# Sheet1.net
KiCad netlist of a schematic drawn in Altium Designer
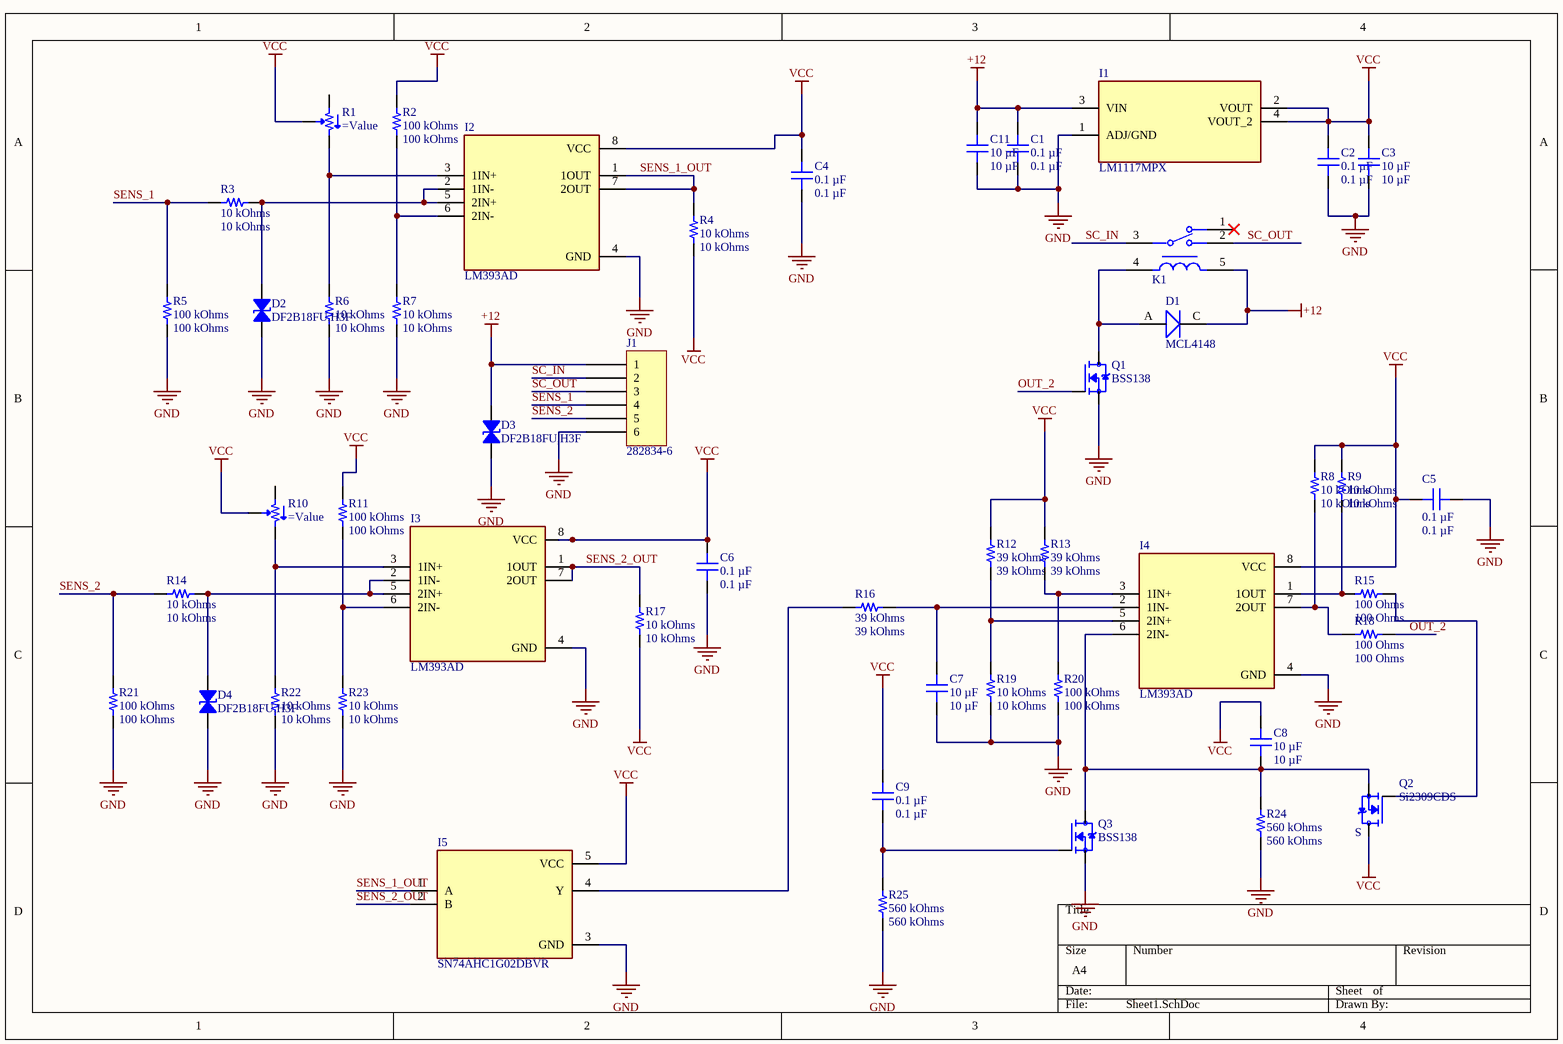
[diagram p0: Sheet1.SchDoc]

(export (version "E")
  (design (tool "Eeschema 10.0.6"))
  (components
    (comp (ref "C1")
      (value "0.1 µF")
      (footprint "CAP 0603_1608")
      (description "CAP CER 0.1UF 16V X7R 0603")
      (fields (field (name "PART NUMBER") "0603B104M160CT") (field (name "ALTIUM_VALUE") "0.1 µF"))
      (libsource (lib "Celestial Altium Library - altium_library") (part "Capacitor"))
    )
    (comp (ref "C2")
      (value "0.1 µF")
      (footprint "CAP 0603_1608")
      (description "CAP CER 0.1UF 16V X7R 0603")
      (fields (field (name "PART NUMBER") "0603B104M160CT") (field (name "ALTIUM_VALUE") "0.1 µF"))
      (libsource (lib "Celestial Altium Library - altium_library") (part "Capacitor"))
    )
    (comp (ref "C3")
      (value "10 µF")
      (footprint "CAP 1206_3216 - 0.8MM")
      (description "CAP CER 10UF 16V X7R 1206")
      (fields (field (name "PART NUMBER") "C1206C106M4RAC7800") (field (name "ALTIUM_VALUE") "10 µF"))
      (libsource (lib "Celestial Altium Library - altium_library") (part "Capacitor"))
    )
    (comp (ref "C4")
      (value "0.1 µF")
      (footprint "CAP 0603_1608")
      (description "CAP CER 0.1UF 16V X7R 0603")
      (fields (field (name "PART NUMBER") "0603B104M160CT") (field (name "ALTIUM_VALUE") "0.1 µF"))
      (libsource (lib "Celestial Altium Library - altium_library") (part "Capacitor"))
    )
    (comp (ref "C5")
      (value "0.1 µF")
      (footprint "CAP 0603_1608")
      (description "CAP CER 0.1UF 16V X7R 0603")
      (fields (field (name "PART NUMBER") "0603B104M160CT") (field (name "ALTIUM_VALUE") "0.1 µF"))
      (libsource (lib "Celestial Altium Library - altium_library") (part "Capacitor"))
    )
    (comp (ref "C6")
      (value "0.1 µF")
      (footprint "CAP 0603_1608")
      (description "CAP CER 0.1UF 16V X7R 0603")
      (fields (field (name "PART NUMBER") "0603B104M160CT") (field (name "ALTIUM_VALUE") "0.1 µF"))
      (libsource (lib "Celestial Altium Library - altium_library") (part "Capacitor"))
    )
    (comp (ref "C7")
      (value "10 µF")
      (footprint "CAP 1206_3216 - 0.8MM")
      (description "CAP CER 10UF 16V X7R 1206")
      (fields (field (name "PART NUMBER") "C1206C106M4RAC7800") (field (name "ALTIUM_VALUE") "10 µF"))
      (libsource (lib "Celestial Altium Library - altium_library") (part "Capacitor"))
    )
    (comp (ref "C8")
      (value "10 µF")
      (footprint "CAP 1206_3216 - 0.8MM")
      (description "CAP CER 10UF 16V X7R 1206")
      (fields (field (name "PART NUMBER") "C1206C106M4RAC7800") (field (name "ALTIUM_VALUE") "10 µF"))
      (libsource (lib "Celestial Altium Library - altium_library") (part "Capacitor"))
    )
    (comp (ref "C9")
      (value "0.1 µF")
      (footprint "CAP 0603_1608")
      (description "CAP CER 0.1UF 16V X7R 0603")
      (fields (field (name "PART NUMBER") "0603B104M160CT") (field (name "ALTIUM_VALUE") "0.1 µF"))
      (libsource (lib "Celestial Altium Library - altium_library") (part "Capacitor"))
    )
    (comp (ref "C11")
      (value "10 µF")
      (footprint "CAP 1206_3216 - 0.8MM")
      (description "CAP CER 10UF 16V X7R 1206")
      (fields (field (name "PART NUMBER") "C1206C106M4RAC7800") (field (name "ALTIUM_VALUE") "10 µF"))
      (libsource (lib "Celestial Altium Library - altium_library") (part "Capacitor"))
    )
    (comp (ref "D1") (value "MCL4148") (footprint "MC4148") (libsource (lib "Schlib1") (part "MCL4148")))
    (comp (ref "D2")
      (value "DF2B18FU,H3F")
      (footprint "SOD323")
      (description "TVS DIODE 12VWM 33VC USC")
      (libsource (lib "Celestial Altium Library - altium_library") (part "Diode TVS"))
    )
    (comp (ref "D3")
      (value "DF2B18FU,H3F")
      (footprint "SOD323")
      (description "TVS DIODE 12VWM 33VC USC")
      (libsource (lib "Celestial Altium Library - altium_library") (part "Diode TVS"))
    )
    (comp (ref "D4")
      (value "DF2B18FU,H3F")
      (footprint "SOD323")
      (description "TVS DIODE 12VWM 33VC USC")
      (libsource (lib "Celestial Altium Library - altium_library") (part "Diode TVS"))
    )
    (comp (ref "I1") (value "LM1117MPX") (footprint "LM1117") (libsource (lib "Schlib1") (part "LM1117MPX")))
    (comp (ref "I2")
      (value "LM393AD")
      (footprint "PCBComponent_1")
      (libsource (lib "Schlib1") (part "LM393AD"))
    )
    (comp (ref "I3")
      (value "LM393AD")
      (footprint "PCBComponent_1")
      (libsource (lib "Schlib1") (part "LM393AD"))
    )
    (comp (ref "I4")
      (value "LM393AD")
      (footprint "PCBComponent_1")
      (libsource (lib "Schlib1") (part "LM393AD"))
    )
    (comp (ref "I5")
      (value "SN74AHC1G02DBVR")
      (footprint "PCBComponent_1 - duplicate")
      (libsource (lib "Schlib1") (part "SN74AHC1G02DBVR"))
    )
    (comp (ref "J1")
      (value "282834-6")
      (footprint "TE 282834-6")
      (description "TERM BLK 6P SIDE ENT 2.54MM PCB")
      (libsource (lib "Celestial Altium Library - altium_library") (part "6 Pin"))
    )
    (comp (ref "K1")
      (value "CP1-12V")
      (footprint "Panasonic_0_MFG")
      (description "Relays 12VDC 225Ohm 20(NO)/10(NC)A SPDT(14mm 13mm 9.5mm) THT Automotive Relay Automotive")
      (fields (field (name "DIGIKEY PART NUMBER") "255-1939-ND") (field (name "MANUFACTURER") "Panasonic"))
      (libsource (lib "EEConcierge") (part "CP1-12V"))
    )
    (comp (ref "Q1") (value "BSS138") (footprint "BSS138") (libsource (lib "Schlib1") (part "BSS138")))
    (comp (ref "Q2") (value "Si2309CDS") (footprint "BSS138") (libsource (lib "Schlib1") (part "Si2309CDS")))
    (comp (ref "Q3") (value "BSS138") (footprint "BSS138") (libsource (lib "Schlib1") (part "BSS138")))
    (comp (ref "R1")
      (value "~")
      (footprint "BOURNS TRIMPOT 3296W")
      (description "TRIMMER 20K OHM 0.5W PC PIN TOP")
      (fields (field (name "PART NUMBER") "3296W-1-203A"))
      (libsource (lib "Celestial Altium Library - altium_library") (part "Potentiometer"))
    )
    (comp (ref "R2")
      (value "100 kOhms")
      (footprint "RES 0603_1608")
      (description "RES 100K OHM 1% 1/10W 0603")
      (fields (field (name "PART NUMBER") "AC0603FR-10100KL") (field (name "ALTIUM_VALUE") "100 kOhms"))
      (libsource (lib "Celestial Altium Library - altium_library") (part "Resistor"))
    )
    (comp (ref "R3")
      (value "10 kOhms")
      (footprint "RES 0603_1608")
      (description "RES 10K OHM 2% 1/3W 0603")
      (fields (field (name "PART NUMBER") "SG73P1JTTD103G") (field (name "ALTIUM_VALUE") "10 kOhms"))
      (libsource (lib "Celestial Altium Library - altium_library") (part "Resistor"))
    )
    (comp (ref "R4")
      (value "10 kOhms")
      (footprint "RES 0603_1608")
      (description "RES 10K OHM 2% 1/3W 0603")
      (fields (field (name "PART NUMBER") "SG73P1JTTD103G") (field (name "ALTIUM_VALUE") "10 kOhms"))
      (libsource (lib "Celestial Altium Library - altium_library") (part "Resistor"))
    )
    (comp (ref "R5")
      (value "100 kOhms")
      (footprint "RES 0603_1608")
      (description "RES 100K OHM 1% 1/10W 0603")
      (fields (field (name "PART NUMBER") "AC0603FR-10100KL") (field (name "ALTIUM_VALUE") "100 kOhms"))
      (libsource (lib "Celestial Altium Library - altium_library") (part "Resistor"))
    )
    (comp (ref "R6")
      (value "10 kOhms")
      (footprint "RES 0603_1608")
      (description "RES 10K OHM 2% 1/3W 0603")
      (fields (field (name "PART NUMBER") "SG73P1JTTD103G") (field (name "ALTIUM_VALUE") "10 kOhms"))
      (libsource (lib "Celestial Altium Library - altium_library") (part "Resistor"))
    )
    (comp (ref "R7")
      (value "10 kOhms")
      (footprint "RES 0603_1608")
      (description "RES 10K OHM 2% 1/3W 0603")
      (fields (field (name "PART NUMBER") "SG73P1JTTD103G") (field (name "ALTIUM_VALUE") "10 kOhms"))
      (libsource (lib "Celestial Altium Library - altium_library") (part "Resistor"))
    )
    (comp (ref "R8")
      (value "10 kOhms")
      (footprint "RES 0603_1608")
      (description "RES 10K OHM 2% 1/3W 0603")
      (fields (field (name "PART NUMBER") "SG73P1JTTD103G") (field (name "ALTIUM_VALUE") "10 kOhms"))
      (libsource (lib "Celestial Altium Library - altium_library") (part "Resistor"))
    )
    (comp (ref "R9")
      (value "10 kOhms")
      (footprint "RES 0603_1608")
      (description "RES 10K OHM 2% 1/3W 0603")
      (fields (field (name "PART NUMBER") "SG73P1JTTD103G") (field (name "ALTIUM_VALUE") "10 kOhms"))
      (libsource (lib "Celestial Altium Library - altium_library") (part "Resistor"))
    )
    (comp (ref "R10")
      (value "~")
      (footprint "BOURNS TRIMPOT 3296W")
      (description "TRIMMER 20K OHM 0.5W PC PIN TOP")
      (fields (field (name "PART NUMBER") "3296W-1-203A"))
      (libsource (lib "Celestial Altium Library - altium_library") (part "Potentiometer"))
    )
    (comp (ref "R11")
      (value "100 kOhms")
      (footprint "RES 0603_1608")
      (description "RES 100K OHM 1% 1/10W 0603")
      (fields (field (name "PART NUMBER") "AC0603FR-10100KL") (field (name "ALTIUM_VALUE") "100 kOhms"))
      (libsource (lib "Celestial Altium Library - altium_library") (part "Resistor"))
    )
    (comp (ref "R12")
      (value "39 kOhms")
      (footprint "RES 0603_1608")
      (description "RES 39K OHM 1% 1/8W 0603")
      (fields (field (name "PART NUMBER") "ERJ-H3EF3902V") (field (name "ALTIUM_VALUE") "39 kOhms"))
      (libsource (lib "Celestial Altium Library - altium_library") (part "Resistor"))
    )
    (comp (ref "R13")
      (value "39 kOhms")
      (footprint "RES 0603_1608")
      (description "RES 39K OHM 1% 1/8W 0603")
      (fields (field (name "PART NUMBER") "ERJ-H3EF3902V") (field (name "ALTIUM_VALUE") "39 kOhms"))
      (libsource (lib "Celestial Altium Library - altium_library") (part "Resistor"))
    )
    (comp (ref "R14")
      (value "10 kOhms")
      (footprint "RES 0603_1608")
      (description "RES 10K OHM 2% 1/3W 0603")
      (fields (field (name "PART NUMBER") "SG73P1JTTD103G") (field (name "ALTIUM_VALUE") "10 kOhms"))
      (libsource (lib "Celestial Altium Library - altium_library") (part "Resistor"))
    )
    (comp (ref "R15")
      (value "100 Ohms")
      (footprint "RES 0603_1608")
      (description "RES 100 OHM 5% 1/8W 0603")
      (fields (field (name "PART NUMBER") "RK73B1JRTTD101J") (field (name "ALTIUM_VALUE") "100 Ohms"))
      (libsource (lib "Celestial Altium Library - altium_library") (part "Resistor"))
    )
    (comp (ref "R16")
      (value "39 kOhms")
      (footprint "RES 0603_1608")
      (description "RES 39K OHM 1% 1/8W 0603")
      (fields (field (name "PART NUMBER") "ERJ-H3EF3902V") (field (name "ALTIUM_VALUE") "39 kOhms"))
      (libsource (lib "Celestial Altium Library - altium_library") (part "Resistor"))
    )
    (comp (ref "R17")
      (value "10 kOhms")
      (footprint "RES 0603_1608")
      (description "RES 10K OHM 2% 1/3W 0603")
      (fields (field (name "PART NUMBER") "SG73P1JTTD103G") (field (name "ALTIUM_VALUE") "10 kOhms"))
      (libsource (lib "Celestial Altium Library - altium_library") (part "Resistor"))
    )
    (comp (ref "R18")
      (value "100 Ohms")
      (footprint "RES 0603_1608")
      (description "RES 100 OHM 5% 1/8W 0603")
      (fields (field (name "PART NUMBER") "RK73B1JRTTD101J") (field (name "ALTIUM_VALUE") "100 Ohms"))
      (libsource (lib "Celestial Altium Library - altium_library") (part "Resistor"))
    )
    (comp (ref "R19")
      (value "10 kOhms")
      (footprint "RES 0603_1608")
      (description "RES 10K OHM 2% 1/3W 0603")
      (fields (field (name "PART NUMBER") "SG73P1JTTD103G") (field (name "ALTIUM_VALUE") "10 kOhms"))
      (libsource (lib "Celestial Altium Library - altium_library") (part "Resistor"))
    )
    (comp (ref "R20")
      (value "100 kOhms")
      (footprint "RES 0603_1608")
      (description "RES 100K OHM 1% 1/10W 0603")
      (fields (field (name "PART NUMBER") "AC0603FR-10100KL") (field (name "ALTIUM_VALUE") "100 kOhms"))
      (libsource (lib "Celestial Altium Library - altium_library") (part "Resistor"))
    )
    (comp (ref "R21")
      (value "100 kOhms")
      (footprint "RES 0603_1608")
      (description "RES 100K OHM 1% 1/10W 0603")
      (fields (field (name "PART NUMBER") "AC0603FR-10100KL") (field (name "ALTIUM_VALUE") "100 kOhms"))
      (libsource (lib "Celestial Altium Library - altium_library") (part "Resistor"))
    )
    (comp (ref "R22")
      (value "10 kOhms")
      (footprint "RES 0603_1608")
      (description "RES 10K OHM 2% 1/3W 0603")
      (fields (field (name "PART NUMBER") "SG73P1JTTD103G") (field (name "ALTIUM_VALUE") "10 kOhms"))
      (libsource (lib "Celestial Altium Library - altium_library") (part "Resistor"))
    )
    (comp (ref "R23")
      (value "10 kOhms")
      (footprint "RES 0603_1608")
      (description "RES 10K OHM 2% 1/3W 0603")
      (fields (field (name "PART NUMBER") "SG73P1JTTD103G") (field (name "ALTIUM_VALUE") "10 kOhms"))
      (libsource (lib "Celestial Altium Library - altium_library") (part "Resistor"))
    )
    (comp (ref "R24")
      (value "560 kOhms")
      (footprint "RES 0603_1608")
      (description "RES SMD 560K OHM 1% 1/4W 0603")
      (fields (field (name "PART NUMBER") "RCS0603560KFKEA") (field (name "ALTIUM_VALUE") "560 kOhms"))
      (libsource (lib "Celestial Altium Library - altium_library") (part "Resistor"))
    )
    (comp (ref "R25")
      (value "560 kOhms")
      (footprint "RES 0603_1608")
      (description "RES SMD 560K OHM 1% 1/4W 0603")
      (fields (field (name "PART NUMBER") "RCS0603560KFKEA") (field (name "ALTIUM_VALUE") "560 kOhms"))
      (libsource (lib "Celestial Altium Library - altium_library") (part "Resistor"))
    )
  )
  (nets
    (net (code "1") (name "+12") (class "Default")
      (node (ref "C1") (pin "2") (pinfunction "2_2") (pintype "passive"))
      (node (ref "C11") (pin "2") (pinfunction "2_2") (pintype "passive"))
      (node (ref "D1") (pin "C") (pinfunction "K_C") (pintype "open_collector"))
      (node (ref "D3") (pin "2") (pinfunction "2_2") (pintype "passive"))
      (node (ref "I1") (pin "3") (pinfunction "VIN_3") (pintype "open_collector"))
      (node (ref "J1") (pin "1") (pinfunction "1_1") (pintype "passive"))
      (node (ref "K1") (pin "5") (pinfunction "COIL_5") (pintype "passive"))
    )
    (net (code "2") (name "/OUT_2") (class "Default")
      (node (ref "Q1") (pin "1") (pinfunction "G_1") (pintype "open_collector"))
      (node (ref "R18") (pin "2") (pinfunction "2_2") (pintype "passive"))
    )
    (net (code "3") (name "/SC_IN") (class "Default")
      (node (ref "J1") (pin "2") (pinfunction "2_2") (pintype "passive"))
      (node (ref "K1") (pin "3") (pinfunction "COM_3") (pintype "passive"))
    )
    (net (code "4") (name "/SC_OUT") (class "Default")
      (node (ref "J1") (pin "3") (pinfunction "3_3") (pintype "passive"))
      (node (ref "K1") (pin "2") (pinfunction "NO_2") (pintype "passive"))
    )
    (net (code "5") (name "/SENS_1") (class "Default")
      (node (ref "J1") (pin "4") (pinfunction "4_4") (pintype "passive"))
      (node (ref "R3") (pin "1") (pinfunction "1_1") (pintype "passive"))
      (node (ref "R5") (pin "2") (pinfunction "2_2") (pintype "passive"))
    )
    (net (code "6") (name "/SENS_1_OUT") (class "Default")
      (node (ref "I2") (pin "1") (pinfunction "1OUT_1") (pintype "open_collector"))
      (node (ref "I2") (pin "7") (pinfunction "2OUT_7") (pintype "open_collector"))
      (node (ref "I5") (pin "1") (pinfunction "A_1") (pintype "open_collector"))
      (node (ref "R4") (pin "1") (pinfunction "1_1") (pintype "passive"))
    )
    (net (code "7") (name "/SENS_2") (class "Default")
      (node (ref "J1") (pin "5") (pinfunction "5_5") (pintype "passive"))
      (node (ref "R14") (pin "2") (pinfunction "2_2") (pintype "passive"))
      (node (ref "R21") (pin "2") (pinfunction "2_2") (pintype "passive"))
    )
    (net (code "8") (name "/SENS_2_OUT") (class "Default")
      (node (ref "I3") (pin "1") (pinfunction "1OUT_1") (pintype "open_collector"))
      (node (ref "I3") (pin "7") (pinfunction "2OUT_7") (pintype "open_collector"))
      (node (ref "I5") (pin "2") (pinfunction "B_2") (pintype "open_collector"))
      (node (ref "R17") (pin "2") (pinfunction "2_2") (pintype "passive"))
    )
    (net (code "9") (name "GND") (class "Default")
      (node (ref "C1") (pin "1") (pinfunction "1_1") (pintype "passive"))
      (node (ref "C11") (pin "1") (pinfunction "1_1") (pintype "passive"))
      (node (ref "C2") (pin "1") (pinfunction "1_1") (pintype "passive"))
      (node (ref "C3") (pin "1") (pinfunction "1_1") (pintype "passive"))
      (node (ref "C4") (pin "2") (pinfunction "2_2") (pintype "passive"))
      (node (ref "C5") (pin "2") (pinfunction "2_2") (pintype "passive"))
      (node (ref "C6") (pin "2") (pinfunction "2_2") (pintype "passive"))
      (node (ref "C7") (pin "1") (pinfunction "1_1") (pintype "passive"))
      (node (ref "D2") (pin "1") (pinfunction "1_1") (pintype "passive"))
      (node (ref "D3") (pin "1") (pinfunction "1_1") (pintype "passive"))
      (node (ref "D4") (pin "1") (pinfunction "1_1") (pintype "passive"))
      (node (ref "I1") (pin "1") (pinfunction "ADJ/GND_1") (pintype "open_collector"))
      (node (ref "I2") (pin "4") (pinfunction "GND_4") (pintype "open_collector"))
      (node (ref "I3") (pin "4") (pinfunction "GND_4") (pintype "open_collector"))
      (node (ref "I4") (pin "4") (pinfunction "GND_4") (pintype "open_collector"))
      (node (ref "I5") (pin "3") (pinfunction "GND_3") (pintype "open_collector"))
      (node (ref "J1") (pin "6") (pinfunction "6_6") (pintype "passive"))
      (node (ref "Q1") (pin "2") (pinfunction "S_2") (pintype "open_collector"))
      (node (ref "Q3") (pin "2") (pinfunction "S_2") (pintype "open_collector"))
      (node (ref "R19") (pin "1") (pinfunction "1_1") (pintype "passive"))
      (node (ref "R20") (pin "1") (pinfunction "1_1") (pintype "passive"))
      (node (ref "R21") (pin "1") (pinfunction "1_1") (pintype "passive"))
      (node (ref "R22") (pin "1") (pinfunction "1_1") (pintype "passive"))
      (node (ref "R23") (pin "1") (pinfunction "1_1") (pintype "passive"))
      (node (ref "R24") (pin "1") (pinfunction "1_1") (pintype "passive"))
      (node (ref "R25") (pin "1") (pinfunction "1_1") (pintype "passive"))
      (node (ref "R5") (pin "1") (pinfunction "1_1") (pintype "passive"))
      (node (ref "R6") (pin "2") (pinfunction "2_2") (pintype "passive"))
      (node (ref "R7") (pin "2") (pinfunction "2_2") (pintype "passive"))
    )
    (net (code "10") (name "Net-(I2-1IN+)") (class "Default")
      (node (ref "I2") (pin "3") (pinfunction "1IN+_3") (pintype "open_collector"))
      (node (ref "R1") (pin "3") (pinfunction "3_3") (pintype "passive"))
      (node (ref "R6") (pin "1") (pinfunction "1_1") (pintype "passive"))
    )
    (net (code "11") (name "Net-(I2-1IN-)") (class "Default")
      (node (ref "D2") (pin "2") (pinfunction "2_2") (pintype "passive"))
      (node (ref "I2") (pin "2") (pinfunction "1IN-_2") (pintype "open_collector"))
      (node (ref "I2") (pin "5") (pinfunction "2IN+_5") (pintype "open_collector"))
      (node (ref "R3") (pin "2") (pinfunction "2_2") (pintype "passive"))
    )
    (net (code "12") (name "Net-(I2-2IN-)") (class "Default")
      (node (ref "I2") (pin "6") (pinfunction "2IN-_6") (pintype "open_collector"))
      (node (ref "R2") (pin "1") (pinfunction "1_1") (pintype "passive"))
      (node (ref "R7") (pin "1") (pinfunction "1_1") (pintype "passive"))
    )
    (net (code "13") (name "Net-(I3-1IN+)") (class "Default")
      (node (ref "I3") (pin "3") (pinfunction "1IN+_3") (pintype "open_collector"))
      (node (ref "R10") (pin "3") (pinfunction "3_3") (pintype "passive"))
      (node (ref "R22") (pin "2") (pinfunction "2_2") (pintype "passive"))
    )
    (net (code "14") (name "Net-(I3-1IN-)") (class "Default")
      (node (ref "D4") (pin "2") (pinfunction "2_2") (pintype "passive"))
      (node (ref "I3") (pin "2") (pinfunction "1IN-_2") (pintype "open_collector"))
      (node (ref "I3") (pin "5") (pinfunction "2IN+_5") (pintype "open_collector"))
      (node (ref "R14") (pin "1") (pinfunction "1_1") (pintype "passive"))
    )
    (net (code "15") (name "Net-(I3-2IN-)") (class "Default")
      (node (ref "I3") (pin "6") (pinfunction "2IN-_6") (pintype "open_collector"))
      (node (ref "R11") (pin "1") (pinfunction "1_1") (pintype "passive"))
      (node (ref "R23") (pin "2") (pinfunction "2_2") (pintype "passive"))
    )
    (net (code "16") (name "Net-(I4-1IN+)") (class "Default")
      (node (ref "I4") (pin "3") (pinfunction "1IN+_3") (pintype "open_collector"))
      (node (ref "R13") (pin "1") (pinfunction "1_1") (pintype "passive"))
      (node (ref "R20") (pin "2") (pinfunction "2_2") (pintype "passive"))
    )
    (net (code "17") (name "Net-(I4-1IN-)") (class "Default")
      (node (ref "C7") (pin "2") (pinfunction "2_2") (pintype "passive"))
      (node (ref "I4") (pin "2") (pinfunction "1IN-_2") (pintype "open_collector"))
      (node (ref "R16") (pin "2") (pinfunction "2_2") (pintype "passive"))
    )
    (net (code "18") (name "Net-(I4-1OUT)") (class "Default")
      (node (ref "I4") (pin "1") (pinfunction "1OUT_1") (pintype "open_collector"))
      (node (ref "R15") (pin "1") (pinfunction "1_1") (pintype "passive"))
      (node (ref "R9") (pin "1") (pinfunction "1_1") (pintype "passive"))
    )
    (net (code "19") (name "Net-(I4-2IN+)") (class "Default")
      (node (ref "I4") (pin "5") (pinfunction "2IN+_5") (pintype "open_collector"))
      (node (ref "R12") (pin "1") (pinfunction "1_1") (pintype "passive"))
      (node (ref "R19") (pin "2") (pinfunction "2_2") (pintype "passive"))
    )
    (net (code "20") (name "Net-(I4-2IN-)") (class "Default")
      (node (ref "C8") (pin "1") (pinfunction "1_1") (pintype "passive"))
      (node (ref "I4") (pin "6") (pinfunction "2IN-_6") (pintype "open_collector"))
      (node (ref "Q2") (pin "2") (pinfunction "S_2") (pintype "open_collector"))
      (node (ref "Q3") (pin "3") (pinfunction "D_3") (pintype "open_collector"))
      (node (ref "R24") (pin "2") (pinfunction "2_2") (pintype "passive"))
    )
    (net (code "21") (name "Net-(I4-2OUT)") (class "Default")
      (node (ref "I4") (pin "7") (pinfunction "2OUT_7") (pintype "open_collector"))
      (node (ref "R18") (pin "1") (pinfunction "1_1") (pintype "passive"))
      (node (ref "R8") (pin "1") (pinfunction "1_1") (pintype "passive"))
    )
    (net (code "22") (name "Net-(I5-Y)") (class "Default")
      (node (ref "I5") (pin "4") (pinfunction "Y_4") (pintype "open_collector"))
      (node (ref "R16") (pin "1") (pinfunction "1_1") (pintype "passive"))
    )
    (net (code "23") (name "Net-(Q1-D)") (class "Default")
      (node (ref "D1") (pin "A") (pinfunction "A_A") (pintype "open_collector"))
      (node (ref "K1") (pin "4") (pinfunction "COIL_4") (pintype "passive"))
      (node (ref "Q1") (pin "3") (pinfunction "D_3") (pintype "open_collector"))
    )
    (net (code "24") (name "Net-(Q2-G)") (class "Default")
      (node (ref "Q2") (pin "1") (pinfunction "G_1") (pintype "open_collector"))
      (node (ref "R15") (pin "2") (pinfunction "2_2") (pintype "passive"))
    )
    (net (code "25") (name "Net-(Q3-G)") (class "Default")
      (node (ref "C9") (pin "2") (pinfunction "2_2") (pintype "passive"))
      (node (ref "Q3") (pin "1") (pinfunction "G_1") (pintype "open_collector"))
      (node (ref "R25") (pin "2") (pinfunction "2_2") (pintype "passive"))
    )
    (net (code "26") (name "VCC") (class "Default")
      (node (ref "C2") (pin "2") (pinfunction "2_2") (pintype "passive"))
      (node (ref "C3") (pin "2") (pinfunction "2_2") (pintype "passive"))
      (node (ref "C4") (pin "1") (pinfunction "1_1") (pintype "passive"))
      (node (ref "C5") (pin "1") (pinfunction "1_1") (pintype "passive"))
      (node (ref "C6") (pin "1") (pinfunction "1_1") (pintype "passive"))
      (node (ref "C8") (pin "2") (pinfunction "2_2") (pintype "passive"))
      (node (ref "C9") (pin "1") (pinfunction "1_1") (pintype "passive"))
      (node (ref "I1") (pin "2") (pinfunction "VOUT_2") (pintype "open_collector"))
      (node (ref "I1") (pin "4") (pinfunction "VOUT_2_4") (pintype "open_collector"))
      (node (ref "I2") (pin "8") (pinfunction "VCC_8") (pintype "open_collector"))
      (node (ref "I3") (pin "8") (pinfunction "VCC_8") (pintype "open_collector"))
      (node (ref "I4") (pin "8") (pinfunction "VCC_8") (pintype "open_collector"))
      (node (ref "I5") (pin "5") (pinfunction "VCC_5") (pintype "open_collector"))
      (node (ref "Q2") (pin "3") (pinfunction "D_3") (pintype "open_collector"))
      (node (ref "R1") (pin "2") (pinfunction "2_2") (pintype "passive"))
      (node (ref "R10") (pin "2") (pinfunction "2_2") (pintype "passive"))
      (node (ref "R11") (pin "2") (pinfunction "2_2") (pintype "passive"))
      (node (ref "R12") (pin "2") (pinfunction "2_2") (pintype "passive"))
      (node (ref "R13") (pin "2") (pinfunction "2_2") (pintype "passive"))
      (node (ref "R17") (pin "1") (pinfunction "1_1") (pintype "passive"))
      (node (ref "R2") (pin "2") (pinfunction "2_2") (pintype "passive"))
      (node (ref "R4") (pin "2") (pinfunction "2_2") (pintype "passive"))
      (node (ref "R8") (pin "2") (pinfunction "2_2") (pintype "passive"))
      (node (ref "R9") (pin "2") (pinfunction "2_2") (pintype "passive"))
    )
    (net (code "27") (name "unconnected-(K1-NC-Pad1)") (class "Default")
      (node (ref "K1") (pin "1") (pinfunction "NC_1") (pintype "passive+no_connect"))
    )
    (net (code "28") (name "unconnected-(R1-Pad1)") (class "Default")
      (node (ref "R1") (pin "1") (pinfunction "1_1") (pintype "passive"))
    )
    (net (code "29") (name "unconnected-(R10-Pad1)") (class "Default")
      (node (ref "R10") (pin "1") (pinfunction "1_1") (pintype "passive"))
    )
  )
)
